# Develop328.net
KiCad netlist of a schematic drawn in EAGLE
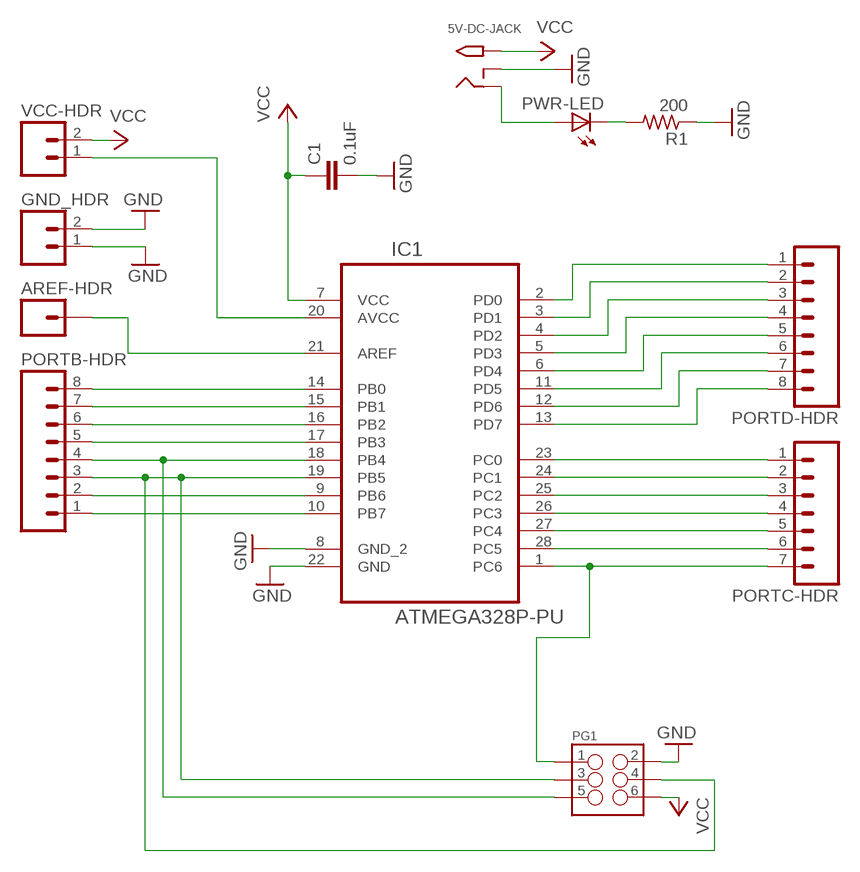
[diagram p0: schematic, sheet 1]

(export (version "E")
  (design (tool "Eeschema 10.0.6"))
  (components
    (comp (ref "5V-DC-JACK")
      (value "2.1MMJACKTHM")
      (footprint "eagle-import:PJ-102A")
      (libsource (lib "eagle-import") (part "2.1MMJACKTHM"))
    )
    (comp (ref "AREF-HDR")
      (value "M01PTH")
      (footprint "eagle-import:1X01")
      (libsource (lib "eagle-import") (part "M01PTH"))
    )
    (comp (ref "C1")
      (value "0.1uF")
      (footprint "eagle-import:CAP-PTH-SMALL-KIT")
      (libsource (lib "eagle-import") (part "0.1UF-50V-20%(PTH)KIT-EZ"))
    )
    (comp (ref "GND_HDR")
      (value "M02PTH")
      (footprint "eagle-import:1X02")
      (libsource (lib "eagle-import") (part "M02PTH"))
    )
    (comp (ref "IC1")
      (value "ATMEGA328P-PU")
      (footprint "eagle-import:DIP254P762X457-28")
      (libsource (lib "eagle-import") (part "ATMEGA328P-PU"))
    )
    (comp (ref "PG1")
      (value "M03X2SHROUD")
      (footprint "eagle-import:2X3-SHROUDED")
      (libsource (lib "eagle-import") (part "M03X2SHROUD"))
    )
    (comp (ref "PORTB-HDR")
      (value "M08")
      (footprint "eagle-import:1X08_ROUND")
      (libsource (lib "eagle-import") (part "M08"))
    )
    (comp (ref "PORTC-HDR")
      (value "M07")
      (footprint "eagle-import:1X07")
      (libsource (lib "eagle-import") (part "M07"))
    )
    (comp (ref "PORTD-HDR")
      (value "M08")
      (footprint "eagle-import:1X08_ROUND")
      (libsource (lib "eagle-import") (part "M08"))
    )
    (comp (ref "PWR-LED")
      (value "LED3MM")
      (footprint "eagle-import:LED3MM")
      (libsource (lib "eagle-import") (part "LED3MM"))
    )
    (comp (ref "R1")
      (value "200")
      (footprint "eagle-import:0204_5")
      (libsource (lib "eagle-import") (part "R-US_0204/5"))
    )
    (comp (ref "VCC-HDR")
      (value "M02PTH")
      (footprint "eagle-import:1X02")
      (libsource (lib "eagle-import") (part "M02PTH"))
    )
  )
  (nets
    (net (code "1") (name "GND") (class "Default")
      (node (ref "5V-DC-JACK") (pin "RING_SW") (pinfunction "RING_SW_RING_SW") (pintype "bidirectional"))
      (node (ref "C1") (pin "2") (pinfunction "2_2") (pintype "passive"))
      (node (ref "GND_HDR") (pin "1") (pinfunction "1_1") (pintype "passive"))
      (node (ref "GND_HDR") (pin "2") (pinfunction "2_2") (pintype "passive"))
      (node (ref "IC1") (pin "22") (pinfunction "GND_22") (pintype "passive"))
      (node (ref "IC1") (pin "8") (pinfunction "GND_2_8") (pintype "passive"))
      (node (ref "PG1") (pin "2") (pinfunction "2_2") (pintype "bidirectional"))
      (node (ref "R1") (pin "1") (pinfunction "1_1") (pintype "passive"))
    )
    (net (code "2") (name "Net-(5V-DC-JACK-PadRING)") (class "Default")
      (node (ref "5V-DC-JACK") (pin "RING") (pinfunction "RING_RING") (pintype "bidirectional"))
      (node (ref "PWR-LED") (pin "A") (pinfunction "A_A") (pintype "passive"))
    )
    (net (code "3") (name "Net-(IC1-AREF)") (class "Default")
      (node (ref "AREF-HDR") (pin "1") (pinfunction "1_1") (pintype "passive"))
      (node (ref "IC1") (pin "21") (pinfunction "AREF_21") (pintype "input"))
    )
    (net (code "4") (name "Net-(IC1-AVCC)") (class "Default")
      (node (ref "IC1") (pin "20") (pinfunction "AVCC_20") (pintype "power_in"))
      (node (ref "VCC-HDR") (pin "1") (pinfunction "1_1") (pintype "passive"))
    )
    (net (code "5") (name "Net-(IC1-PB0)") (class "Default")
      (node (ref "IC1") (pin "14") (pinfunction "PB0_14") (pintype "bidirectional"))
      (node (ref "PORTB-HDR") (pin "8") (pinfunction "8_8") (pintype "passive"))
    )
    (net (code "6") (name "Net-(IC1-PB1)") (class "Default")
      (node (ref "IC1") (pin "15") (pinfunction "PB1_15") (pintype "bidirectional"))
      (node (ref "PORTB-HDR") (pin "7") (pinfunction "7_7") (pintype "passive"))
    )
    (net (code "7") (name "Net-(IC1-PB2)") (class "Default")
      (node (ref "IC1") (pin "16") (pinfunction "PB2_16") (pintype "bidirectional"))
      (node (ref "PORTB-HDR") (pin "6") (pinfunction "6_6") (pintype "passive"))
    )
    (net (code "8") (name "Net-(IC1-PB3)") (class "Default")
      (node (ref "IC1") (pin "17") (pinfunction "PB3_17") (pintype "bidirectional"))
      (node (ref "PORTB-HDR") (pin "5") (pinfunction "5_5") (pintype "passive"))
    )
    (net (code "9") (name "Net-(IC1-PB4)") (class "Default")
      (node (ref "IC1") (pin "18") (pinfunction "PB4_18") (pintype "bidirectional"))
      (node (ref "PG1") (pin "5") (pinfunction "5_5") (pintype "bidirectional"))
      (node (ref "PORTB-HDR") (pin "4") (pinfunction "4_4") (pintype "passive"))
    )
    (net (code "10") (name "Net-(IC1-PB5)") (class "Default")
      (node (ref "IC1") (pin "19") (pinfunction "PB5_19") (pintype "bidirectional"))
      (node (ref "PG1") (pin "3") (pinfunction "3_3") (pintype "bidirectional"))
      (node (ref "PG1") (pin "4") (pinfunction "4_4") (pintype "bidirectional"))
      (node (ref "PORTB-HDR") (pin "3") (pinfunction "3_3") (pintype "passive"))
    )
    (net (code "11") (name "Net-(IC1-PB6)") (class "Default")
      (node (ref "IC1") (pin "9") (pinfunction "PB6_9") (pintype "bidirectional"))
      (node (ref "PORTB-HDR") (pin "2") (pinfunction "2_2") (pintype "passive"))
    )
    (net (code "12") (name "Net-(IC1-PB7)") (class "Default")
      (node (ref "IC1") (pin "10") (pinfunction "PB7_10") (pintype "bidirectional"))
      (node (ref "PORTB-HDR") (pin "1") (pinfunction "1_1") (pintype "passive"))
    )
    (net (code "13") (name "Net-(IC1-PC0)") (class "Default")
      (node (ref "IC1") (pin "23") (pinfunction "PC0_23") (pintype "bidirectional"))
      (node (ref "PORTC-HDR") (pin "1") (pinfunction "1_1") (pintype "passive"))
    )
    (net (code "14") (name "Net-(IC1-PC1)") (class "Default")
      (node (ref "IC1") (pin "24") (pinfunction "PC1_24") (pintype "bidirectional"))
      (node (ref "PORTC-HDR") (pin "2") (pinfunction "2_2") (pintype "passive"))
    )
    (net (code "15") (name "Net-(IC1-PC2)") (class "Default")
      (node (ref "IC1") (pin "25") (pinfunction "PC2_25") (pintype "bidirectional"))
      (node (ref "PORTC-HDR") (pin "3") (pinfunction "3_3") (pintype "passive"))
    )
    (net (code "16") (name "Net-(IC1-PC3)") (class "Default")
      (node (ref "IC1") (pin "26") (pinfunction "PC3_26") (pintype "bidirectional"))
      (node (ref "PORTC-HDR") (pin "4") (pinfunction "4_4") (pintype "passive"))
    )
    (net (code "17") (name "Net-(IC1-PC4)") (class "Default")
      (node (ref "IC1") (pin "27") (pinfunction "PC4_27") (pintype "bidirectional"))
      (node (ref "PORTC-HDR") (pin "5") (pinfunction "5_5") (pintype "passive"))
    )
    (net (code "18") (name "Net-(IC1-PC5)") (class "Default")
      (node (ref "IC1") (pin "28") (pinfunction "PC5_28") (pintype "bidirectional"))
      (node (ref "PORTC-HDR") (pin "6") (pinfunction "6_6") (pintype "passive"))
    )
    (net (code "19") (name "Net-(IC1-PC6)") (class "Default")
      (node (ref "IC1") (pin "1") (pinfunction "PC6_1") (pintype "bidirectional"))
      (node (ref "PG1") (pin "1") (pinfunction "1_1") (pintype "bidirectional"))
      (node (ref "PORTC-HDR") (pin "7") (pinfunction "7_7") (pintype "passive"))
    )
    (net (code "20") (name "Net-(IC1-PD0)") (class "Default")
      (node (ref "IC1") (pin "2") (pinfunction "PD0_2") (pintype "bidirectional"))
      (node (ref "PORTD-HDR") (pin "1") (pinfunction "1_1") (pintype "passive"))
    )
    (net (code "21") (name "Net-(IC1-PD1)") (class "Default")
      (node (ref "IC1") (pin "3") (pinfunction "PD1_3") (pintype "bidirectional"))
      (node (ref "PORTD-HDR") (pin "2") (pinfunction "2_2") (pintype "passive"))
    )
    (net (code "22") (name "Net-(IC1-PD2)") (class "Default")
      (node (ref "IC1") (pin "4") (pinfunction "PD2_4") (pintype "bidirectional"))
      (node (ref "PORTD-HDR") (pin "3") (pinfunction "3_3") (pintype "passive"))
    )
    (net (code "23") (name "Net-(IC1-PD3)") (class "Default")
      (node (ref "IC1") (pin "5") (pinfunction "PD3_5") (pintype "bidirectional"))
      (node (ref "PORTD-HDR") (pin "4") (pinfunction "4_4") (pintype "passive"))
    )
    (net (code "24") (name "Net-(IC1-PD4)") (class "Default")
      (node (ref "IC1") (pin "6") (pinfunction "PD4_6") (pintype "bidirectional"))
      (node (ref "PORTD-HDR") (pin "5") (pinfunction "5_5") (pintype "passive"))
    )
    (net (code "25") (name "Net-(IC1-PD5)") (class "Default")
      (node (ref "IC1") (pin "11") (pinfunction "PD5_11") (pintype "bidirectional"))
      (node (ref "PORTD-HDR") (pin "6") (pinfunction "6_6") (pintype "passive"))
    )
    (net (code "26") (name "Net-(IC1-PD6)") (class "Default")
      (node (ref "IC1") (pin "12") (pinfunction "PD6_12") (pintype "bidirectional"))
      (node (ref "PORTD-HDR") (pin "7") (pinfunction "7_7") (pintype "passive"))
    )
    (net (code "27") (name "Net-(IC1-PD7)") (class "Default")
      (node (ref "IC1") (pin "13") (pinfunction "PD7_13") (pintype "bidirectional"))
      (node (ref "PORTD-HDR") (pin "8") (pinfunction "8_8") (pintype "passive"))
    )
    (net (code "28") (name "Net-(PWR-LED-C)") (class "Default")
      (node (ref "PWR-LED") (pin "K") (pinfunction "C_K") (pintype "passive"))
      (node (ref "R1") (pin "2") (pinfunction "2_2") (pintype "passive"))
    )
    (net (code "29") (name "VCC") (class "Default")
      (node (ref "5V-DC-JACK") (pin "TIP") (pinfunction "TIP_TIP") (pintype "bidirectional"))
      (node (ref "C1") (pin "1") (pinfunction "1_1") (pintype "passive"))
      (node (ref "IC1") (pin "7") (pinfunction "VCC_7") (pintype "power_in"))
      (node (ref "PG1") (pin "6") (pinfunction "6_6") (pintype "bidirectional"))
      (node (ref "VCC-HDR") (pin "2") (pinfunction "2_2") (pintype "passive"))
    )
  )
)
